# Main.net
KiCad netlist of a schematic drawn in EAGLE
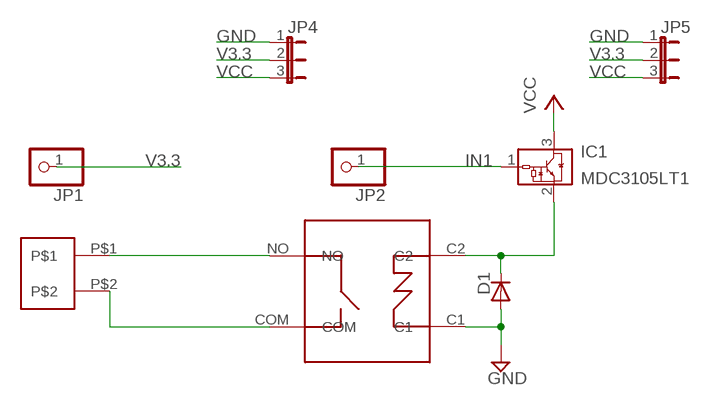
[diagram p0: schematic, sheet 1]

(export (version "E")
  (design (tool "Eeschema 10.0.6"))
  (components
    (comp (ref "D1")
      (value "DIODE-SOD123")
      (footprint "eagle-import:SOD123")
      (libsource (lib "eagle-import") (part "DIODE-SOD123"))
    )
    (comp (ref "IC1")
      (value "MDC3105LT1")
      (footprint "eagle-import:SOT23")
      (fields (field (name "MF") "ON SEMICONDUCTOR"))
      (libsource (lib "eagle-import") (part "MDC3105LT1"))
    )
    (comp (ref "JP1")
      (value "PINHD-1X1")
      (footprint "eagle-import:1X01")
      (libsource (lib "eagle-import") (part "PINHD-1X1"))
    )
    (comp (ref "JP2")
      (value "PINHD-1X1")
      (footprint "eagle-import:1X01")
      (libsource (lib "eagle-import") (part "PINHD-1X1"))
    )
    (comp (ref "JP4")
      (value "JP2E")
      (footprint "eagle-import:JP2")
      (libsource (lib "eagle-import") (part "JP2E"))
    )
    (comp (ref "JP5")
      (value "JP2E")
      (footprint "eagle-import:JP2")
      (libsource (lib "eagle-import") (part "JP2E"))
    )
    (comp (ref "REL1")
      (value "ALQ305")
      (footprint "eagle-import:ALQ305")
      (libsource (lib "eagle-import") (part "ALQ305"))
    )
    (comp (ref "U$2")
      (value "1713017")
      (footprint "eagle-import:1713017")
      (libsource (lib "eagle-import") (part "1713017"))
    )
  )
  (nets
    (net (code "1") (name "/IN1") (class "Default")
      (node (ref "IC1") (pin "1") (pinfunction "VIN_1") (pintype "passive"))
      (node (ref "JP2") (pin "1") (pinfunction "1_1") (pintype "passive"))
    )
    (net (code "2") (name "/V3.3") (class "Default")
      (node (ref "JP1") (pin "1") (pinfunction "1_1") (pintype "passive"))
      (node (ref "JP4") (pin "2") (pinfunction "2_2") (pintype "passive"))
      (node (ref "JP5") (pin "2") (pinfunction "2_2") (pintype "passive"))
    )
    (net (code "3") (name "GND") (class "Default")
      (node (ref "D1") (pin "A") (pinfunction "A_A") (pintype "passive"))
      (node (ref "JP4") (pin "1") (pinfunction "1_1") (pintype "passive"))
      (node (ref "JP5") (pin "1") (pinfunction "1_1") (pintype "passive"))
      (node (ref "REL1") (pin "C1") (pinfunction "C1_C1") (pintype "bidirectional"))
    )
    (net (code "4") (name "Net-(IC1-GND)") (class "Default")
      (node (ref "D1") (pin "C") (pinfunction "C_C") (pintype "passive"))
      (node (ref "IC1") (pin "2") (pinfunction "GND_2") (pintype "passive"))
      (node (ref "REL1") (pin "C2") (pinfunction "C2_C2") (pintype "bidirectional"))
    )
    (net (code "5") (name "Net-(REL1-PadCOM)") (class "Default")
      (node (ref "REL1") (pin "COM") (pinfunction "COM_COM") (pintype "bidirectional"))
      (node (ref "U$2") (pin "P$2") (pinfunction "P$2_P$2") (pintype "power_in"))
    )
    (net (code "6") (name "Net-(REL1-PadNO)") (class "Default")
      (node (ref "REL1") (pin "NO") (pinfunction "NO_NO") (pintype "bidirectional"))
      (node (ref "U$2") (pin "P$1") (pinfunction "P$1_P$1") (pintype "power_in"))
    )
    (net (code "7") (name "VCC") (class "Default")
      (node (ref "IC1") (pin "3") (pinfunction "VOUT_3") (pintype "passive"))
      (node (ref "JP4") (pin "3") (pinfunction "3_3") (pintype "passive"))
      (node (ref "JP5") (pin "3") (pinfunction "3_3") (pintype "passive"))
    )
  )
)
